# TransBoard.net
KiCad netlist of a schematic drawn in Altium Designer
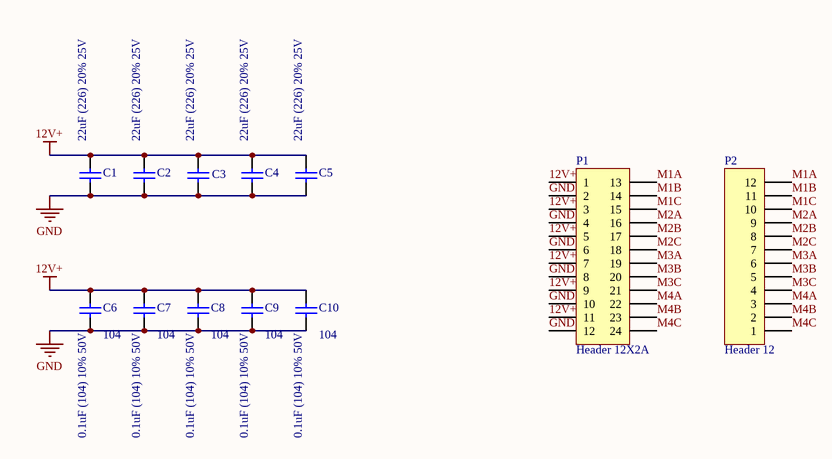
[diagram p0: TransBoard.SchDoc]

(export (version "E")
  (design (tool "Eeschema 10.0.6"))
  (components
    (comp (ref "C1")
      (value "22uF (226) 20% 25V")
      (footprint "0805_C")
      (description "贴片电容")
      (libsource (lib "Miscellaneous Devices LC") (part "0805 22uF (226) 20% 25V"))
    )
    (comp (ref "C2")
      (value "22uF (226) 20% 25V")
      (footprint "0805_C")
      (description "贴片电容")
      (libsource (lib "Miscellaneous Devices LC") (part "0805 22uF (226) 20% 25V"))
    )
    (comp (ref "C3")
      (value "22uF (226) 20% 25V")
      (footprint "0805_C")
      (description "贴片电容")
      (libsource (lib "Miscellaneous Devices LC") (part "0805 22uF (226) 20% 25V"))
    )
    (comp (ref "C4")
      (value "22uF (226) 20% 25V")
      (footprint "0805_C")
      (description "贴片电容")
      (libsource (lib "Miscellaneous Devices LC") (part "0805 22uF (226) 20% 25V"))
    )
    (comp (ref "C5")
      (value "22uF (226) 20% 25V")
      (footprint "0805_C")
      (description "贴片电容")
      (libsource (lib "Miscellaneous Devices LC") (part "0805 22uF (226) 20% 25V"))
    )
    (comp (ref "C6")
      (value "0.1uF (104) 10% 50V")
      (footprint "0805_C")
      (description "Capacitor")
      (fields (field (name "ALTIUM_VALUE") "104") (field (name "PUBLISHER") "Altium Limited"))
      (libsource (lib "Miscellaneous Devices") (part "Cap"))
    )
    (comp (ref "C7")
      (value "0.1uF (104) 10% 50V")
      (footprint "0805_C")
      (description "Capacitor")
      (fields (field (name "ALTIUM_VALUE") "104") (field (name "PUBLISHER") "Altium Limited"))
      (libsource (lib "Miscellaneous Devices") (part "Cap"))
    )
    (comp (ref "C8")
      (value "0.1uF (104) 10% 50V")
      (footprint "0805_C")
      (description "Capacitor")
      (fields (field (name "ALTIUM_VALUE") "104") (field (name "PUBLISHER") "Altium Limited"))
      (libsource (lib "Miscellaneous Devices") (part "Cap"))
    )
    (comp (ref "C9")
      (value "0.1uF (104) 10% 50V")
      (footprint "0805_C")
      (description "Capacitor")
      (fields (field (name "ALTIUM_VALUE") "104") (field (name "PUBLISHER") "Altium Limited"))
      (libsource (lib "Miscellaneous Devices") (part "Cap"))
    )
    (comp (ref "C10")
      (value "0.1uF (104) 10% 50V")
      (footprint "0805_C")
      (description "Capacitor")
      (fields (field (name "ALTIUM_VALUE") "104") (field (name "PUBLISHER") "Altium Limited"))
      (libsource (lib "Miscellaneous Devices") (part "Cap"))
    )
    (comp (ref "P1")
      (value "Header 12X2A")
      (footprint "KF128A")
      (description "Header, 12-Pin, Dual row")
      (fields (field (name "PUBLISHER") "Altium Limited"))
      (libsource (lib "Miscellaneous Connectors") (part "Header 12X2A"))
    )
    (comp (ref "P2")
      (value "Header 12")
      (footprint "KF128A 单排")
      (description "Header, 12-Pin")
      (fields (field (name "PUBLISHER") "Altium Limited"))
      (libsource (lib "Miscellaneous Connectors") (part "Header 12"))
    )
  )
  (nets
    (net (code "1") (name "/M1A") (class "Default")
      (node (ref "P1") (pin "13") (pinfunction "13_13") (pintype "passive"))
      (node (ref "P2") (pin "12") (pinfunction "12_12") (pintype "passive"))
    )
    (net (code "2") (name "/M1B") (class "Default")
      (node (ref "P1") (pin "14") (pinfunction "14_14") (pintype "passive"))
      (node (ref "P2") (pin "11") (pinfunction "11_11") (pintype "passive"))
    )
    (net (code "3") (name "/M1C") (class "Default")
      (node (ref "P1") (pin "15") (pinfunction "15_15") (pintype "passive"))
      (node (ref "P2") (pin "10") (pinfunction "10_10") (pintype "passive"))
    )
    (net (code "4") (name "/M2A") (class "Default")
      (node (ref "P1") (pin "16") (pinfunction "16_16") (pintype "passive"))
      (node (ref "P2") (pin "9") (pinfunction "9_9") (pintype "passive"))
    )
    (net (code "5") (name "/M2B") (class "Default")
      (node (ref "P1") (pin "17") (pinfunction "17_17") (pintype "passive"))
      (node (ref "P2") (pin "8") (pinfunction "8_8") (pintype "passive"))
    )
    (net (code "6") (name "/M2C") (class "Default")
      (node (ref "P1") (pin "18") (pinfunction "18_18") (pintype "passive"))
      (node (ref "P2") (pin "7") (pinfunction "7_7") (pintype "passive"))
    )
    (net (code "7") (name "/M3A") (class "Default")
      (node (ref "P1") (pin "19") (pinfunction "19_19") (pintype "passive"))
      (node (ref "P2") (pin "6") (pinfunction "6_6") (pintype "passive"))
    )
    (net (code "8") (name "/M3B") (class "Default")
      (node (ref "P1") (pin "20") (pinfunction "20_20") (pintype "passive"))
      (node (ref "P2") (pin "5") (pinfunction "5_5") (pintype "passive"))
    )
    (net (code "9") (name "/M3C") (class "Default")
      (node (ref "P1") (pin "21") (pinfunction "21_21") (pintype "passive"))
      (node (ref "P2") (pin "4") (pinfunction "4_4") (pintype "passive"))
    )
    (net (code "10") (name "/M4A") (class "Default")
      (node (ref "P1") (pin "22") (pinfunction "22_22") (pintype "passive"))
      (node (ref "P2") (pin "3") (pinfunction "3_3") (pintype "passive"))
    )
    (net (code "11") (name "/M4B") (class "Default")
      (node (ref "P1") (pin "23") (pinfunction "23_23") (pintype "passive"))
      (node (ref "P2") (pin "2") (pinfunction "2_2") (pintype "passive"))
    )
    (net (code "12") (name "/M4C") (class "Default")
      (node (ref "P1") (pin "24") (pinfunction "24_24") (pintype "passive"))
      (node (ref "P2") (pin "1") (pinfunction "1_1") (pintype "passive"))
    )
    (net (code "13") (name "12V+") (class "Default")
      (node (ref "C1") (pin "2") (pinfunction "2_2") (pintype "passive"))
      (node (ref "C10") (pin "2") (pinfunction "2_2") (pintype "passive"))
      (node (ref "C2") (pin "2") (pinfunction "2_2") (pintype "passive"))
      (node (ref "C3") (pin "2") (pinfunction "2_2") (pintype "passive"))
      (node (ref "C4") (pin "2") (pinfunction "2_2") (pintype "passive"))
      (node (ref "C5") (pin "2") (pinfunction "2_2") (pintype "passive"))
      (node (ref "C6") (pin "2") (pinfunction "2_2") (pintype "passive"))
      (node (ref "C7") (pin "2") (pinfunction "2_2") (pintype "passive"))
      (node (ref "C8") (pin "2") (pinfunction "2_2") (pintype "passive"))
      (node (ref "C9") (pin "2") (pinfunction "2_2") (pintype "passive"))
      (node (ref "P1") (pin "1") (pinfunction "1_1") (pintype "passive"))
      (node (ref "P1") (pin "11") (pinfunction "11_11") (pintype "passive"))
      (node (ref "P1") (pin "3") (pinfunction "3_3") (pintype "passive"))
      (node (ref "P1") (pin "5") (pinfunction "5_5") (pintype "passive"))
      (node (ref "P1") (pin "7") (pinfunction "7_7") (pintype "passive"))
      (node (ref "P1") (pin "9") (pinfunction "9_9") (pintype "passive"))
    )
    (net (code "14") (name "GND") (class "Default")
      (node (ref "C1") (pin "1") (pinfunction "1_1") (pintype "passive"))
      (node (ref "C10") (pin "1") (pinfunction "1_1") (pintype "passive"))
      (node (ref "C2") (pin "1") (pinfunction "1_1") (pintype "passive"))
      (node (ref "C3") (pin "1") (pinfunction "1_1") (pintype "passive"))
      (node (ref "C4") (pin "1") (pinfunction "1_1") (pintype "passive"))
      (node (ref "C5") (pin "1") (pinfunction "1_1") (pintype "passive"))
      (node (ref "C6") (pin "1") (pinfunction "1_1") (pintype "passive"))
      (node (ref "C7") (pin "1") (pinfunction "1_1") (pintype "passive"))
      (node (ref "C8") (pin "1") (pinfunction "1_1") (pintype "passive"))
      (node (ref "C9") (pin "1") (pinfunction "1_1") (pintype "passive"))
      (node (ref "P1") (pin "10") (pinfunction "10_10") (pintype "passive"))
      (node (ref "P1") (pin "12") (pinfunction "12_12") (pintype "passive"))
      (node (ref "P1") (pin "2") (pinfunction "2_2") (pintype "passive"))
      (node (ref "P1") (pin "4") (pinfunction "4_4") (pintype "passive"))
      (node (ref "P1") (pin "6") (pinfunction "6_6") (pintype "passive"))
      (node (ref "P1") (pin "8") (pinfunction "8_8") (pintype "passive"))
    )
  )
)
